# Schematic.net
KiCad netlist of a schematic drawn in EAGLE
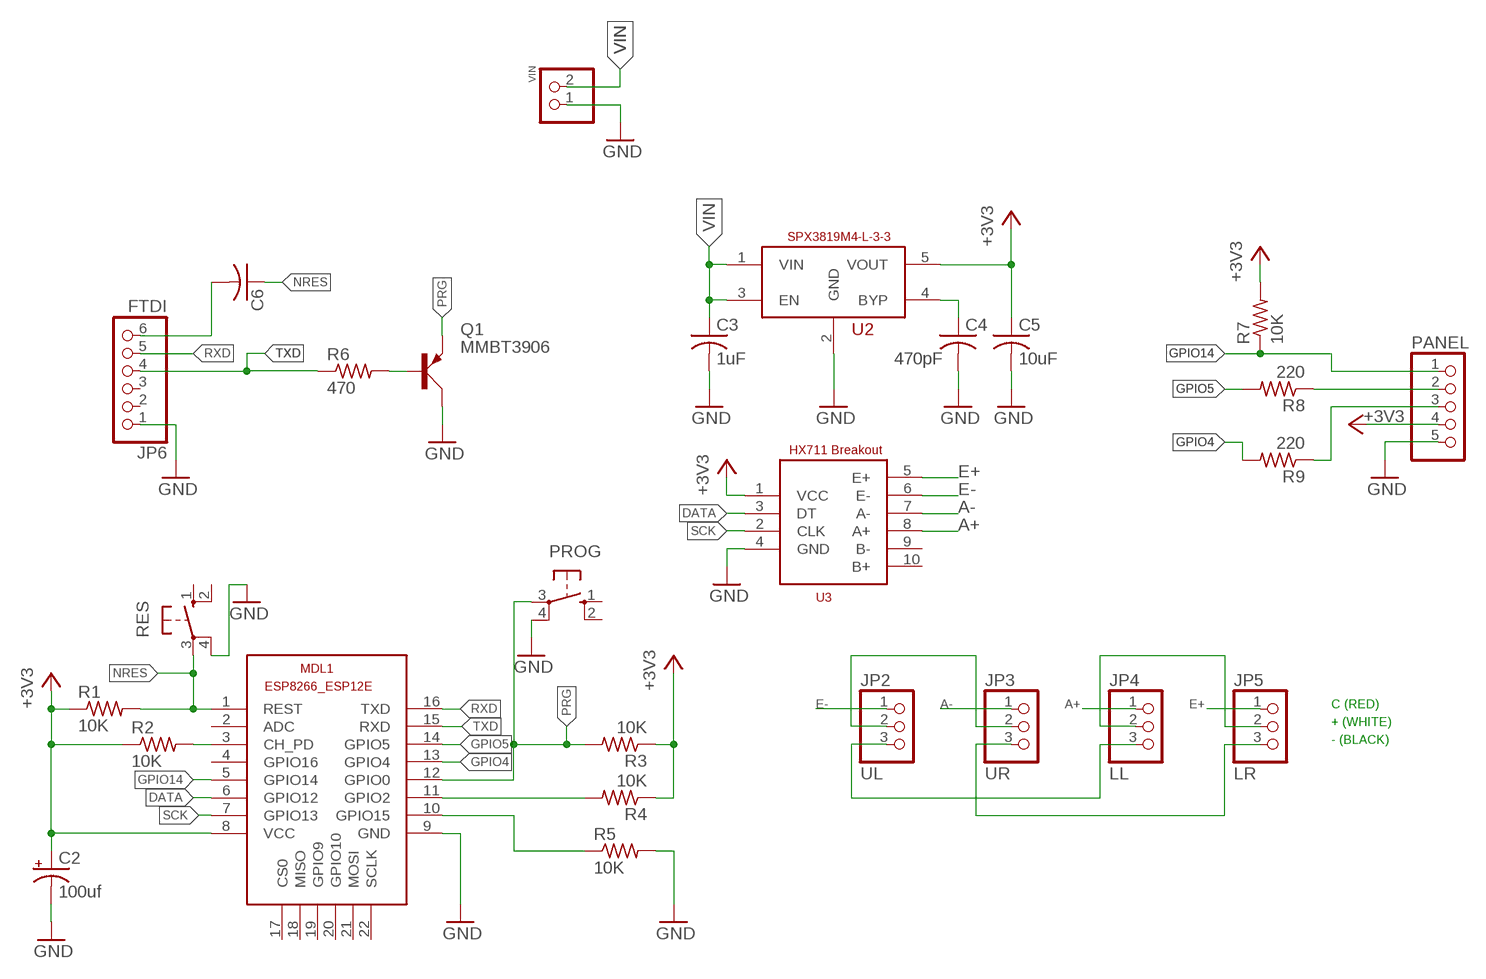
[diagram p0: schematic, sheet 1]

(export (version "E")
  (design (tool "Eeschema 10.0.6"))
  (components
    (comp (ref "C2")
      (value "100uf")
      (footprint "eagle-import:E2,5-6E")
      (libsource (lib "eagle-import") (part "CPOL-USE2,5-6E"))
    )
    (comp (ref "C3")
      (value "1uF")
      (footprint "eagle-import:C0805")
      (libsource (lib "eagle-import") (part "C-USC0805"))
    )
    (comp (ref "C4")
      (value "470pF")
      (footprint "eagle-import:C0805")
      (libsource (lib "eagle-import") (part "C-USC0805"))
    )
    (comp (ref "C5")
      (value "10uF")
      (footprint "eagle-import:C0805")
      (libsource (lib "eagle-import") (part "C-USC0805"))
    )
    (comp (ref "C6")
      (value "100uF")
      (footprint "eagle-import:C025-024X044")
      (libsource (lib "eagle-import") (part "C-US025-024X044"))
    )
    (comp (ref "JP2")
      (value "UL")
      (footprint "eagle-import:1X03")
      (libsource (lib "eagle-import") (part "PINHD-1X3"))
    )
    (comp (ref "JP3")
      (value "UR")
      (footprint "eagle-import:1X03")
      (libsource (lib "eagle-import") (part "PINHD-1X3"))
    )
    (comp (ref "JP4")
      (value "LL")
      (footprint "eagle-import:1X03")
      (libsource (lib "eagle-import") (part "PINHD-1X3"))
    )
    (comp (ref "JP5")
      (value "LR")
      (footprint "eagle-import:1X03")
      (libsource (lib "eagle-import") (part "PINHD-1X3"))
    )
    (comp (ref "JP6")
      (value "FTDI")
      (footprint "eagle-import:1X06")
      (libsource (lib "eagle-import") (part "PINHD-1X6"))
    )
    (comp (ref "MDL1")
      (value "ESP8266-12EESP8266-ESP12E")
      (footprint "eagle-import:ESP8266-ESP12E")
      (libsource (lib "eagle-import") (part "ESP8266-12EESP8266-ESP12E"))
    )
    (comp (ref "PANEL")
      (value "PINHD-1X5")
      (footprint "eagle-import:1X05")
      (libsource (lib "eagle-import") (part "PINHD-1X5"))
    )
    (comp (ref "PROG")
      (value "10-XX")
      (footprint "eagle-import:B3F-10XX")
      (fields (field (name "MPN") "B3F-1000"))
      (libsource (lib "eagle-import") (part "10-XX"))
    )
    (comp (ref "Q1")
      (value "MMBT3906")
      (footprint "eagle-import:TO92D")
      (libsource (lib "eagle-import") (part "2N3906"))
    )
    (comp (ref "R1")
      (value "10K")
      (footprint "eagle-import:R0805")
      (libsource (lib "eagle-import") (part "resistor_348_R-US_R0805"))
    )
    (comp (ref "R2")
      (value "10K")
      (footprint "eagle-import:R0805")
      (libsource (lib "eagle-import") (part "resistor_348_R-US_R0805"))
    )
    (comp (ref "R3")
      (value "10K")
      (footprint "eagle-import:R0805")
      (libsource (lib "eagle-import") (part "resistor_348_R-US_R0805"))
    )
    (comp (ref "R4")
      (value "10K")
      (footprint "eagle-import:R0805")
      (libsource (lib "eagle-import") (part "resistor_348_R-US_R0805"))
    )
    (comp (ref "R5")
      (value "10K")
      (footprint "eagle-import:R0805")
      (libsource (lib "eagle-import") (part "resistor_348_R-US_R0805"))
    )
    (comp (ref "R6")
      (value "470")
      (footprint "eagle-import:R0805")
      (libsource (lib "eagle-import") (part "R-US_R0805"))
    )
    (comp (ref "R7")
      (value "10K")
      (footprint "eagle-import:R0805")
      (libsource (lib "eagle-import") (part "resistor_348_R-US_R0805"))
    )
    (comp (ref "R8")
      (value "220")
      (footprint "eagle-import:R0805")
      (libsource (lib "eagle-import") (part "resistor_348_R-US_R0805"))
    )
    (comp (ref "R9")
      (value "220")
      (footprint "eagle-import:R0805")
      (libsource (lib "eagle-import") (part "resistor_348_R-US_R0805"))
    )
    (comp (ref "RES")
      (value "10-XX")
      (footprint "eagle-import:B3F-10XX")
      (fields (field (name "MPN") "B3F-1000"))
      (libsource (lib "eagle-import") (part "10-XX"))
    )
    (comp (ref "U2")
      (value "SPX3819M5-L-3-3")
      (footprint "eagle-import:SOT23-5L")
      (libsource (lib "eagle-import") (part "SPX3819M5-L-3-3"))
    )
    (comp (ref "U3")
      (value "HX711-BREAKOUT")
      (footprint "eagle-import:HX711-THT")
      (libsource (lib "eagle-import") (part "HX711-BREAKOUT"))
    )
    (comp (ref "VIN")
      (value "PINHD-1X2")
      (footprint "eagle-import:1X02")
      (libsource (lib "eagle-import") (part "PINHD-1X2"))
    )
  )
  (nets
    (net (code "1") (name "+3V3") (class "Default")
      (node (ref "C2") (pin "+") (pinfunction "+_+") (pintype "passive"))
      (node (ref "C5") (pin "1") (pinfunction "1_1") (pintype "passive"))
      (node (ref "MDL1") (pin "8") (pinfunction "VCC_8") (pintype "bidirectional"))
      (node (ref "PANEL") (pin "4") (pinfunction "4_4") (pintype "passive"))
      (node (ref "R1") (pin "1") (pinfunction "1_1") (pintype "passive"))
      (node (ref "R2") (pin "1") (pinfunction "1_1") (pintype "passive"))
      (node (ref "R3") (pin "1") (pinfunction "1_1") (pintype "passive"))
      (node (ref "R4") (pin "1") (pinfunction "1_1") (pintype "passive"))
      (node (ref "R7") (pin "2") (pinfunction "2_2") (pintype "passive"))
      (node (ref "U2") (pin "5") (pinfunction "VOUT_5") (pintype "bidirectional"))
      (node (ref "U3") (pin "1") (pinfunction "VCC_1") (pintype "bidirectional"))
    )
    (net (code "2") (name "/A+") (class "Default")
      (node (ref "JP4") (pin "1") (pinfunction "1_1") (pintype "passive"))
      (node (ref "U3") (pin "8") (pinfunction "A+_8") (pintype "bidirectional"))
    )
    (net (code "3") (name "/A-") (class "Default")
      (node (ref "JP3") (pin "1") (pinfunction "1_1") (pintype "passive"))
      (node (ref "U3") (pin "7") (pinfunction "A-_7") (pintype "bidirectional"))
    )
    (net (code "4") (name "/E+") (class "Default")
      (node (ref "JP5") (pin "1") (pinfunction "1_1") (pintype "passive"))
      (node (ref "U3") (pin "5") (pinfunction "E+_5") (pintype "bidirectional"))
    )
    (net (code "5") (name "/E-") (class "Default")
      (node (ref "JP2") (pin "1") (pinfunction "1_1") (pintype "passive"))
      (node (ref "U3") (pin "6") (pinfunction "E-_6") (pintype "bidirectional"))
    )
    (net (code "6") (name "DATA") (class "Default")
      (node (ref "MDL1") (pin "6") (pinfunction "GPIO12_6") (pintype "bidirectional"))
      (node (ref "U3") (pin "3") (pinfunction "DT_3") (pintype "bidirectional"))
    )
    (net (code "7") (name "GND") (class "Default")
      (node (ref "C2") (pin "-") (pinfunction "-_-") (pintype "passive"))
      (node (ref "C3") (pin "2") (pinfunction "2_2") (pintype "passive"))
      (node (ref "C4") (pin "2") (pinfunction "2_2") (pintype "passive"))
      (node (ref "C5") (pin "2") (pinfunction "2_2") (pintype "passive"))
      (node (ref "JP6") (pin "1") (pinfunction "1_1") (pintype "passive"))
      (node (ref "MDL1") (pin "9") (pinfunction "GND_9") (pintype "bidirectional"))
      (node (ref "PANEL") (pin "5") (pinfunction "5_5") (pintype "passive"))
      (node (ref "PROG") (pin "4") (pinfunction "P1_4") (pintype "passive"))
      (node (ref "Q1") (pin "C") (pinfunction "C_C") (pintype "passive"))
      (node (ref "R5") (pin "2") (pinfunction "2_2") (pintype "passive"))
      (node (ref "RES") (pin "4") (pinfunction "P1_4") (pintype "passive"))
      (node (ref "U2") (pin "2") (pinfunction "GND_2") (pintype "bidirectional"))
      (node (ref "U3") (pin "4") (pinfunction "GND_4") (pintype "bidirectional"))
      (node (ref "VIN") (pin "1") (pinfunction "1_1") (pintype "passive"))
    )
    (net (code "8") (name "GPIO4") (class "Default")
      (node (ref "MDL1") (pin "13") (pinfunction "GPIO4_13") (pintype "bidirectional"))
      (node (ref "R9") (pin "2") (pinfunction "2_2") (pintype "passive"))
    )
    (net (code "9") (name "GPIO5") (class "Default")
      (node (ref "MDL1") (pin "14") (pinfunction "GPIO5_14") (pintype "bidirectional"))
      (node (ref "R8") (pin "2") (pinfunction "2_2") (pintype "passive"))
    )
    (net (code "10") (name "GPIO14") (class "Default")
      (node (ref "MDL1") (pin "5") (pinfunction "GPIO14_5") (pintype "bidirectional"))
      (node (ref "PANEL") (pin "1") (pinfunction "1_1") (pintype "passive"))
      (node (ref "R7") (pin "1") (pinfunction "1_1") (pintype "passive"))
    )
    (net (code "11") (name "NRES") (class "Default")
      (node (ref "C6") (pin "1") (pinfunction "1_1") (pintype "passive"))
      (node (ref "MDL1") (pin "1") (pinfunction "REST_1") (pintype "bidirectional"))
      (node (ref "R1") (pin "2") (pinfunction "2_2") (pintype "passive"))
      (node (ref "RES") (pin "3") (pinfunction "P_3") (pintype "passive"))
    )
    (net (code "12") (name "Net-(C6-Pad2)") (class "Default")
      (node (ref "C6") (pin "2") (pinfunction "2_2") (pintype "passive"))
      (node (ref "JP6") (pin "6") (pinfunction "6_6") (pintype "passive"))
    )
    (net (code "13") (name "Net-(JP2-Pad2)") (class "Default")
      (node (ref "JP2") (pin "2") (pinfunction "2_2") (pintype "passive"))
      (node (ref "JP3") (pin "2") (pinfunction "2_2") (pintype "passive"))
    )
    (net (code "14") (name "Net-(JP2-Pad3)") (class "Default")
      (node (ref "JP2") (pin "3") (pinfunction "3_3") (pintype "passive"))
      (node (ref "JP4") (pin "3") (pinfunction "3_3") (pintype "passive"))
    )
    (net (code "15") (name "Net-(JP3-Pad3)") (class "Default")
      (node (ref "JP3") (pin "3") (pinfunction "3_3") (pintype "passive"))
      (node (ref "JP5") (pin "3") (pinfunction "3_3") (pintype "passive"))
    )
    (net (code "16") (name "Net-(JP4-Pad2)") (class "Default")
      (node (ref "JP4") (pin "2") (pinfunction "2_2") (pintype "passive"))
      (node (ref "JP5") (pin "2") (pinfunction "2_2") (pintype "passive"))
    )
    (net (code "17") (name "Net-(MDL1-CH_PD)") (class "Default")
      (node (ref "MDL1") (pin "3") (pinfunction "CH_PD_3") (pintype "bidirectional"))
      (node (ref "R2") (pin "2") (pinfunction "2_2") (pintype "passive"))
    )
    (net (code "18") (name "Net-(MDL1-GPIO2)") (class "Default")
      (node (ref "MDL1") (pin "11") (pinfunction "GPIO2_11") (pintype "bidirectional"))
      (node (ref "R4") (pin "2") (pinfunction "2_2") (pintype "passive"))
    )
    (net (code "19") (name "Net-(MDL1-GPIO15)") (class "Default")
      (node (ref "MDL1") (pin "10") (pinfunction "GPIO15_10") (pintype "bidirectional"))
      (node (ref "R5") (pin "1") (pinfunction "1_1") (pintype "passive"))
    )
    (net (code "20") (name "Net-(PANEL-Pad2)") (class "Default")
      (node (ref "PANEL") (pin "2") (pinfunction "2_2") (pintype "passive"))
      (node (ref "R8") (pin "1") (pinfunction "1_1") (pintype "passive"))
    )
    (net (code "21") (name "Net-(PANEL-Pad3)") (class "Default")
      (node (ref "PANEL") (pin "3") (pinfunction "3_3") (pintype "passive"))
      (node (ref "R9") (pin "1") (pinfunction "1_1") (pintype "passive"))
    )
    (net (code "22") (name "Net-(Q1-PadB)") (class "Default")
      (node (ref "Q1") (pin "B") (pinfunction "B_B") (pintype "passive"))
      (node (ref "R6") (pin "2") (pinfunction "2_2") (pintype "passive"))
    )
    (net (code "23") (name "Net-(U2-BYP)") (class "Default")
      (node (ref "C4") (pin "1") (pinfunction "1_1") (pintype "passive"))
      (node (ref "U2") (pin "4") (pinfunction "BYP_4") (pintype "bidirectional"))
    )
    (net (code "24") (name "PRG") (class "Default")
      (node (ref "MDL1") (pin "12") (pinfunction "GPIO0_12") (pintype "bidirectional"))
      (node (ref "PROG") (pin "3") (pinfunction "P_3") (pintype "passive"))
      (node (ref "Q1") (pin "E") (pinfunction "E_E") (pintype "passive"))
      (node (ref "R3") (pin "2") (pinfunction "2_2") (pintype "passive"))
    )
    (net (code "25") (name "RXD") (class "Default")
      (node (ref "JP6") (pin "5") (pinfunction "5_5") (pintype "passive"))
      (node (ref "MDL1") (pin "16") (pinfunction "TXD_16") (pintype "bidirectional"))
    )
    (net (code "26") (name "SCK") (class "Default")
      (node (ref "MDL1") (pin "7") (pinfunction "GPIO13_7") (pintype "bidirectional"))
      (node (ref "U3") (pin "2") (pinfunction "CLK_2") (pintype "bidirectional"))
    )
    (net (code "27") (name "TXD") (class "Default")
      (node (ref "JP6") (pin "4") (pinfunction "4_4") (pintype "passive"))
      (node (ref "MDL1") (pin "15") (pinfunction "RXD_15") (pintype "bidirectional"))
      (node (ref "R6") (pin "1") (pinfunction "1_1") (pintype "passive"))
    )
    (net (code "28") (name "VIN") (class "Default")
      (node (ref "C3") (pin "1") (pinfunction "1_1") (pintype "passive"))
      (node (ref "U2") (pin "1") (pinfunction "VIN_1") (pintype "bidirectional"))
      (node (ref "U2") (pin "3") (pinfunction "EN_3") (pintype "bidirectional"))
      (node (ref "VIN") (pin "2") (pinfunction "2_2") (pintype "passive"))
    )
    (net (code "29") (name "unconnected-(JP6-Pad2)") (class "Default")
      (node (ref "JP6") (pin "2") (pinfunction "2_2") (pintype "passive"))
    )
    (net (code "30") (name "unconnected-(JP6-Pad3)") (class "Default")
      (node (ref "JP6") (pin "3") (pinfunction "3_3") (pintype "passive"))
    )
    (net (code "31") (name "unconnected-(MDL1-ADC-Pad2)") (class "Default")
      (node (ref "MDL1") (pin "2") (pinfunction "ADC_2") (pintype "bidirectional"))
    )
    (net (code "32") (name "unconnected-(MDL1-CS0-Pad17)") (class "Default")
      (node (ref "MDL1") (pin "17") (pinfunction "CS0_17") (pintype "bidirectional"))
    )
    (net (code "33") (name "unconnected-(MDL1-GPIO9-Pad19)") (class "Default")
      (node (ref "MDL1") (pin "19") (pinfunction "GPIO9_19") (pintype "bidirectional"))
    )
    (net (code "34") (name "unconnected-(MDL1-GPIO10-Pad20)") (class "Default")
      (node (ref "MDL1") (pin "20") (pinfunction "GPIO10_20") (pintype "bidirectional"))
    )
    (net (code "35") (name "unconnected-(MDL1-GPIO16-Pad4)") (class "Default")
      (node (ref "MDL1") (pin "4") (pinfunction "GPIO16_4") (pintype "bidirectional"))
    )
    (net (code "36") (name "unconnected-(MDL1-MISO-Pad18)") (class "Default")
      (node (ref "MDL1") (pin "18") (pinfunction "MISO_18") (pintype "bidirectional"))
    )
    (net (code "37") (name "unconnected-(MDL1-MOSI-Pad21)") (class "Default")
      (node (ref "MDL1") (pin "21") (pinfunction "MOSI_21") (pintype "bidirectional"))
    )
    (net (code "38") (name "unconnected-(MDL1-SCLK-Pad22)") (class "Default")
      (node (ref "MDL1") (pin "22") (pinfunction "SCLK_22") (pintype "bidirectional"))
    )
    (net (code "39") (name "unconnected-(PROG-S-Pad1)") (class "Default")
      (node (ref "PROG") (pin "1") (pinfunction "S_1") (pintype "passive"))
    )
    (net (code "40") (name "unconnected-(PROG-S1-Pad2)") (class "Default")
      (node (ref "PROG") (pin "2") (pinfunction "S1_2") (pintype "passive"))
    )
    (net (code "41") (name "unconnected-(RES-S-Pad1)") (class "Default")
      (node (ref "RES") (pin "1") (pinfunction "S_1") (pintype "passive"))
    )
    (net (code "42") (name "unconnected-(RES-S1-Pad2)") (class "Default")
      (node (ref "RES") (pin "2") (pinfunction "S1_2") (pintype "passive"))
    )
    (net (code "43") (name "unconnected-(U3-B+-Pad10)") (class "Default")
      (node (ref "U3") (pin "10") (pinfunction "B+_10") (pintype "bidirectional"))
    )
    (net (code "44") (name "unconnected-(U3-B--Pad9)") (class "Default")
      (node (ref "U3") (pin "9") (pinfunction "B-_9") (pintype "bidirectional"))
    )
  )
)
